# Sheet1.net
KiCad netlist of a schematic drawn in Altium Designer
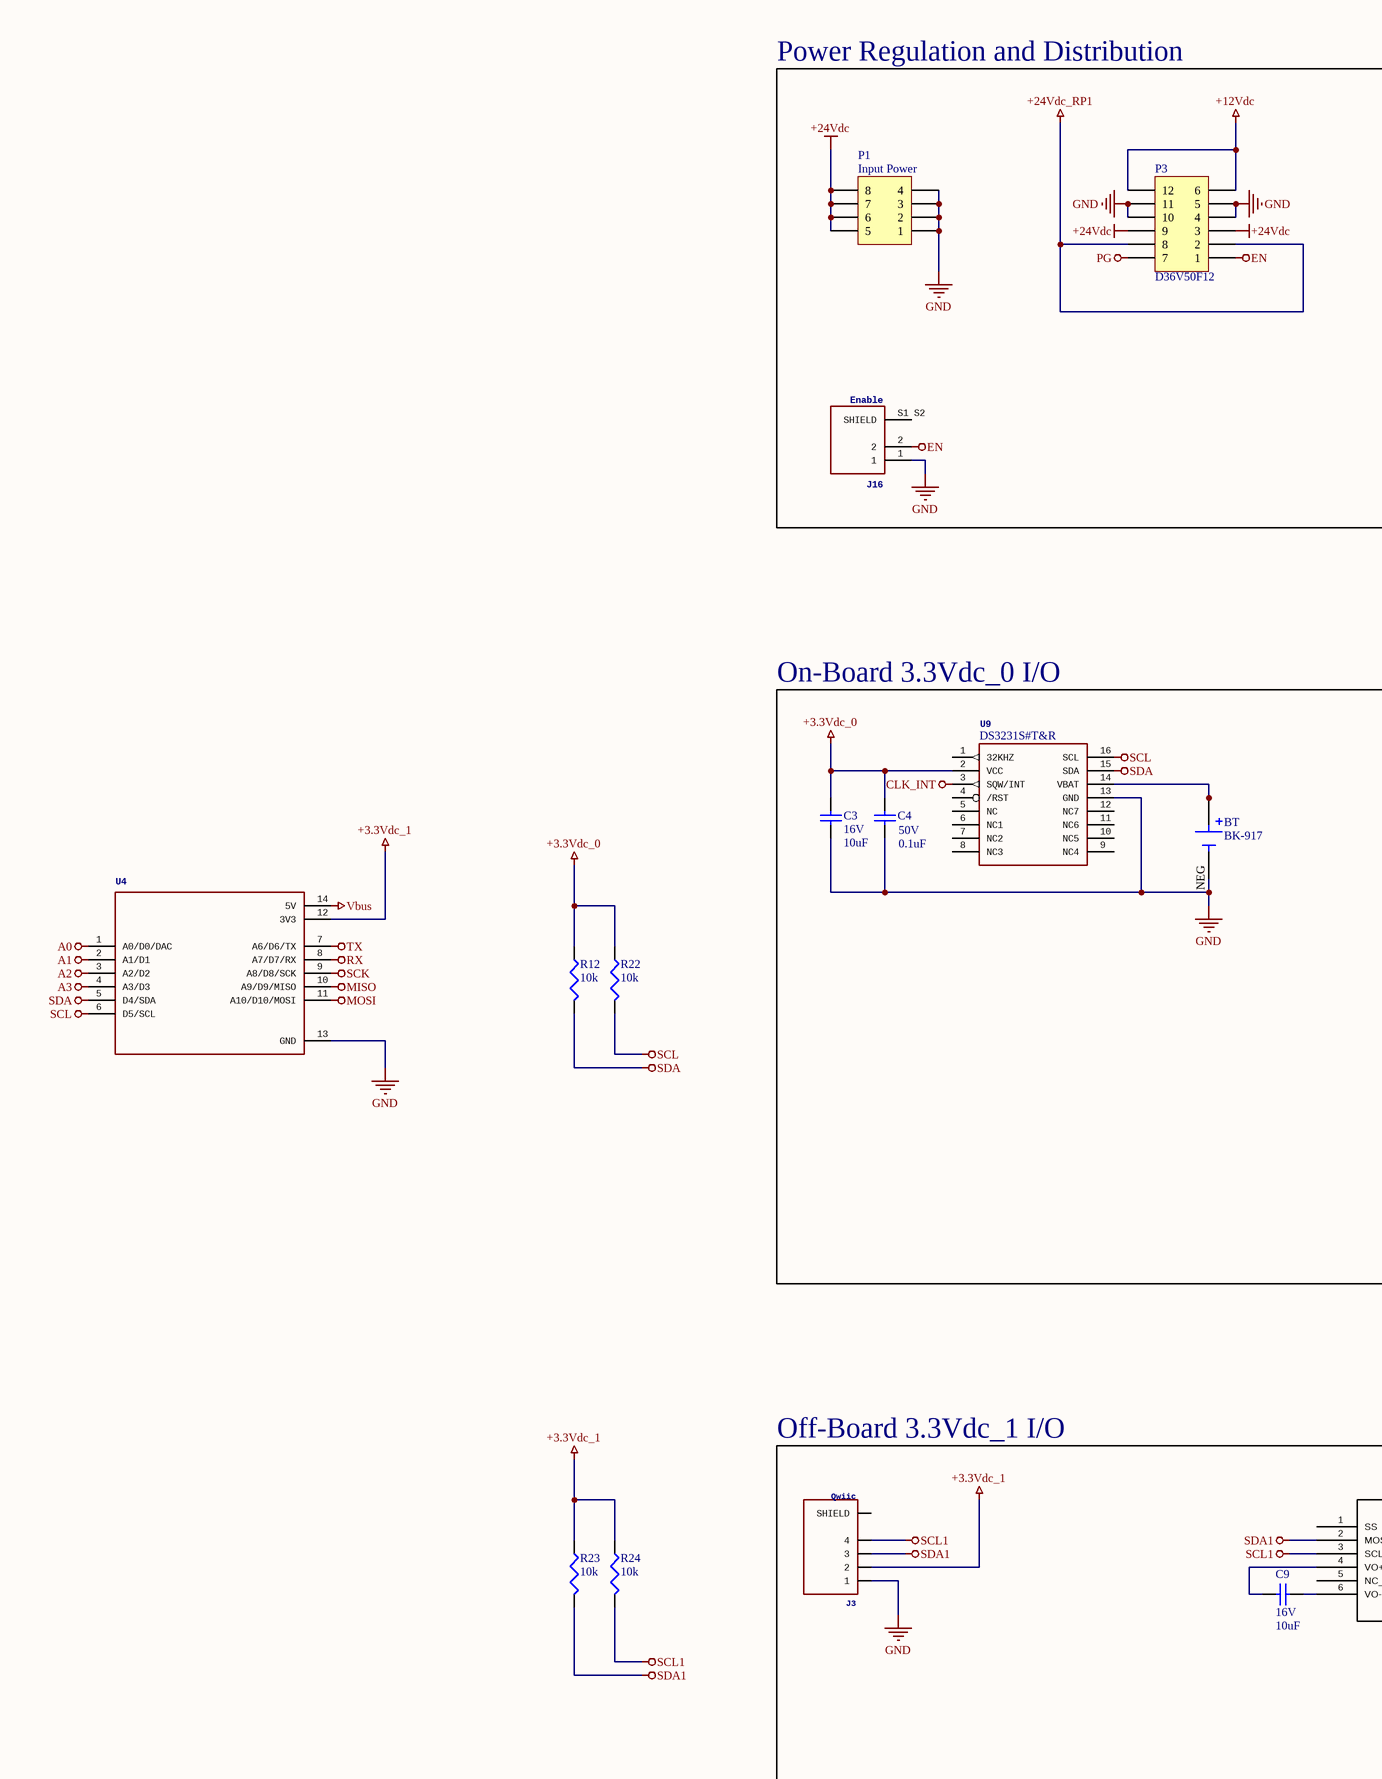
[diagram p0: Sheet1.SchDoc, left]
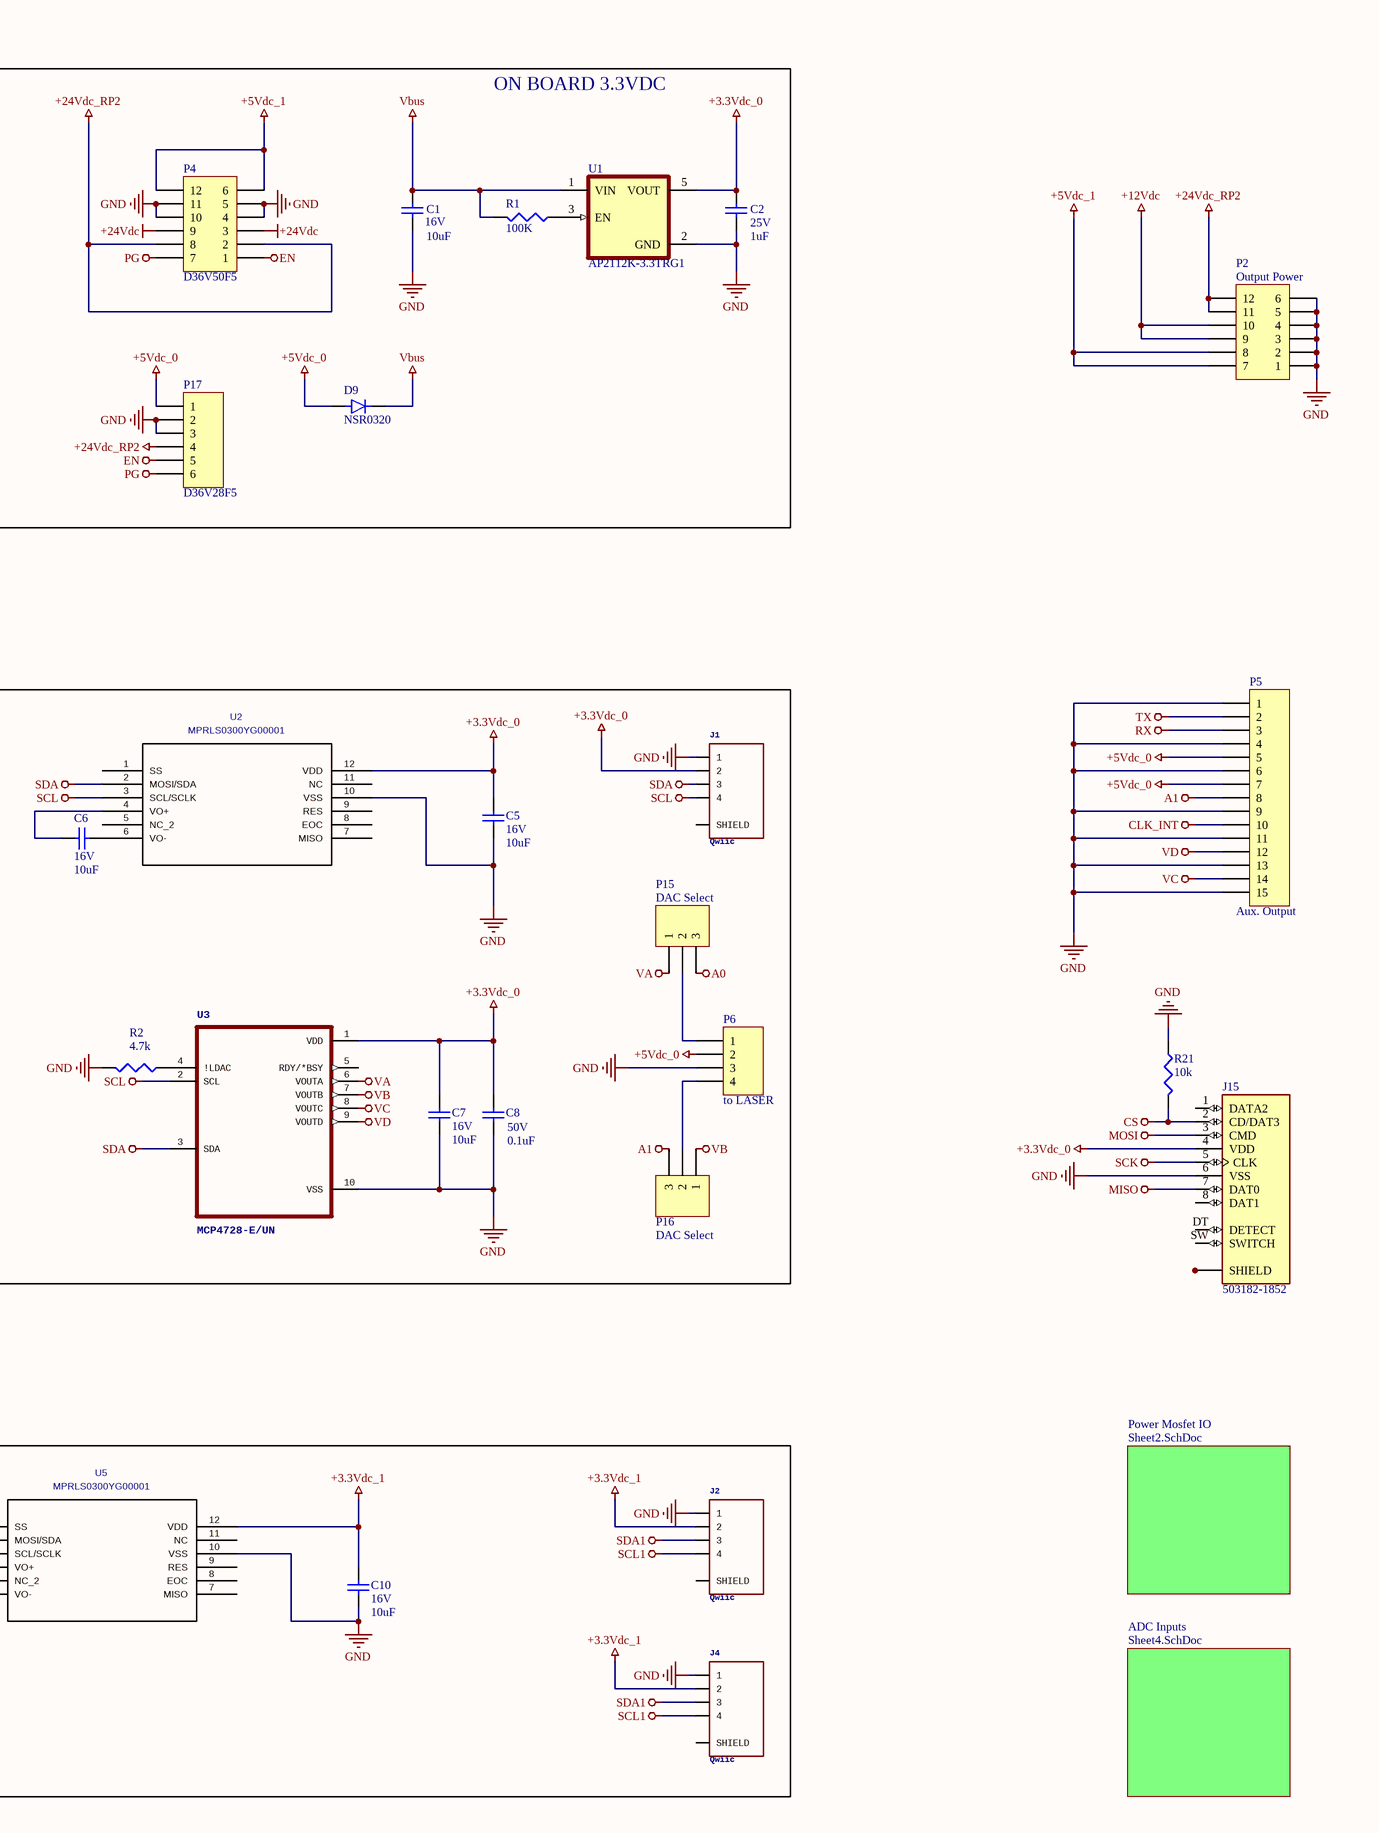
[diagram p1: Sheet1.SchDoc, right]

(export (version "E")
  (design (tool "Eeschema 10.0.6"))
  (components
    (comp (ref "BT")
      (value "BK-917")
      (footprint "BAT_BK-917")
      (description "BATTERY RETAINER COIN PC PIN")
      (fields (field (name "MANUFACTURER") "MPD"))
      (libsource (lib "SnapEDAsch") (part "BK-917"))
    )
    (comp (ref "C1")
      (value "16V")
      (footprint "1608[0603]")
      (description "CAP CER 10UF 16V X5R 0603")
      (fields
        (field (name "ALTIUM_VALUE") "10uF")
        (field (name "MANUFACTURER PART #") "CC0603KRX5R7BB106")
        (field (name "MANUFACTURER") "YAGEO")
      )
      (libsource (lib "Miscellaneous Devices") (part "Cap Semi"))
    )
    (comp (ref "C2")
      (value "25V")
      (footprint "1608[0603]")
      (description "CAP CER 1UF 25V X7R 0603")
      (fields
        (field (name "ALTIUM_VALUE") "1uF")
        (field (name "MANUFACTURER PART #") "AC0603KRX7R8BB105")
        (field (name "MANUFACTURER") "YAGEO")
      )
      (libsource (lib "Miscellaneous Devices") (part "Cap Semi"))
    )
    (comp (ref "C3")
      (value "16V")
      (footprint "1608[0603]")
      (description "CAP CER 10UF 16V X5R 0603")
      (fields
        (field (name "ALTIUM_VALUE") "10uF")
        (field (name "MANUFACTURER PART #") "CC0603KRX5R7BB106")
        (field (name "MANUFACTURER") "YAGEO")
      )
      (libsource (lib "Miscellaneous Devices") (part "Cap Semi"))
    )
    (comp (ref "C4")
      (value "50V")
      (footprint "1608[0603]")
      (description "CAP CER 0.1UF 50V X7R 0603")
      (fields
        (field (name "ALTIUM_VALUE") "0.1uF")
        (field (name "MANUFACTURER PART #") "CC0603KPX7R9BB104")
        (field (name "MANUFACTURER") "YAGEO")
      )
      (libsource (lib "Miscellaneous Devices") (part "Cap Semi"))
    )
    (comp (ref "C5")
      (value "16V")
      (footprint "1608[0603]")
      (description "CAP CER 10UF 16V X5R 0603")
      (fields
        (field (name "ALTIUM_VALUE") "10uF")
        (field (name "MANUFACTURER PART #") "CC0603KRX5R7BB106")
        (field (name "MANUFACTURER") "YAGEO")
      )
      (libsource (lib "Miscellaneous Devices") (part "Cap Semi"))
    )
    (comp (ref "C6")
      (value "16V")
      (footprint "1608[0603]")
      (description "CAP CER 10UF 16V X5R 0603")
      (fields
        (field (name "ALTIUM_VALUE") "10uF")
        (field (name "MANUFACTURER PART #") "CC0603KRX5R7BB106")
        (field (name "MANUFACTURER") "YAGEO")
      )
      (libsource (lib "Miscellaneous Devices") (part "Cap Semi"))
    )
    (comp (ref "C7")
      (value "16V")
      (footprint "1608[0603]")
      (description "CAP CER 10UF 16V X5R 0603")
      (fields
        (field (name "ALTIUM_VALUE") "10uF")
        (field (name "MANUFACTURER PART #") "CC0603KRX5R7BB106")
        (field (name "MANUFACTURER") "YAGEO")
      )
      (libsource (lib "Miscellaneous Devices") (part "Cap Semi"))
    )
    (comp (ref "C8")
      (value "50V")
      (footprint "1608[0603]")
      (description "CAP CER 0.1UF 50V X7R 0603")
      (fields
        (field (name "ALTIUM_VALUE") "0.1uF")
        (field (name "MANUFACTURER PART #") "CC0603KPX7R9BB104")
        (field (name "MANUFACTURER") "YAGEO")
      )
      (libsource (lib "Miscellaneous Devices") (part "Cap Semi"))
    )
    (comp (ref "C9")
      (value "16V")
      (footprint "1608[0603]")
      (description "CAP CER 10UF 16V X5R 0603")
      (fields
        (field (name "ALTIUM_VALUE") "10uF")
        (field (name "MANUFACTURER PART #") "CC0603KRX5R7BB106")
        (field (name "MANUFACTURER") "YAGEO")
      )
      (libsource (lib "Miscellaneous Devices") (part "Cap Semi"))
    )
    (comp (ref "C10")
      (value "16V")
      (footprint "1608[0603]")
      (description "CAP CER 10UF 16V X5R 0603")
      (fields
        (field (name "ALTIUM_VALUE") "10uF")
        (field (name "MANUFACTURER PART #") "CC0603KRX5R7BB106")
        (field (name "MANUFACTURER") "YAGEO")
      )
      (libsource (lib "Miscellaneous Devices") (part "Cap Semi"))
    )
    (comp (ref "D9")
      (value "NSR0320")
      (footprint "DIO_MM3Z3V0T1G")
      (description "DIODE SCHOTTKY 20V 1A SOD323")
      (fields (field (name "MANUFACTURER PART #") "NSR0320MW2T1G") (field (name "MANUFACTURER") "onsemi"))
      (libsource (lib "S1M") (part "S1M"))
    )
    (comp (ref "J1")
      (value "Qwiic")
      (footprint "4P vert")
      (fields
        (field (name "MANUFACTURER PART #") "BM04B-SRSS-TB(LF)(SN)")
        (field (name "MANUFACTURER") "JST Sales")
      )
      (libsource (lib "SM04B-SRSS-TB_LF__SN") (part "SM04B-SRSS-TB(LF)(SN)"))
    )
    (comp (ref "J2")
      (value "Qwiic")
      (footprint "4P vert")
      (fields
        (field (name "MANUFACTURER PART #") "BM04B-SRSS-TB(LF)(SN)")
        (field (name "MANUFACTURER") "JST Sales")
      )
      (libsource (lib "SM04B-SRSS-TB_LF__SN") (part "SM04B-SRSS-TB(LF)(SN)"))
    )
    (comp (ref "J3")
      (value "Qwiic")
      (footprint "JST_SM04B-SRSS-TB(LF)(SN)")
      (fields
        (field (name "MANUFACTURER PART #") "SM04B-SRSS-TB(LF)(SN)")
        (field (name "MANUFACTURER") "JST Sales")
      )
      (libsource (lib "SM04B-SRSS-TB_LF__SN") (part "SM04B-SRSS-TB(LF)(SN)"))
    )
    (comp (ref "J4")
      (value "Qwiic")
      (footprint "JST_SM04B-SRSS-TB(LF)(SN)")
      (fields
        (field (name "MANUFACTURER PART #") "SM04B-SRSS-TB(LF)(SN)")
        (field (name "MANUFACTURER") "JST Sales")
      )
      (libsource (lib "SM04B-SRSS-TB_LF__SN") (part "SM04B-SRSS-TB(LF)(SN)"))
    )
    (comp (ref "J15")
      (value "503182-1852")
      (footprint "MOLEX_503182-1852")
      (description "10 (8 + 2) Position Card Connector Secure Digital - microSDâ„¢ Surface Mount, Right Angle Gold")
      (fields (field (name "MANUFACTURER") "Molex") (field (name "MANUFACTURER PART #") "5031821852"))
      (libsource (lib "503182-1852") (part "503182-1852"))
    )
    (comp (ref "J16")
      (value "Enable")
      (footprint "CONN_BM04B-SRSS-TB(LF)(SN)")
      (fields
        (field (name "MANUFACTURER") "JST Sales")
        (field (name "MANUFACTURER PART #") "BM04B-SRSS-TB(LF)(SN)")
      )
      (libsource (lib "BM02B-SRSS-TB_LF__SN_") (part "BM04B-SRSS-TB(LF)(SN)"))
    )
    (comp (ref "P1")
      (value "Input Power")
      (footprint "2X4 VERTICAL")
      (description "CONN HEADER VERT 8POS 3MM")
      (fields (field (name "MANUFACTURER PART #") "0430450827") (field (name "MANUFACTURER") "Molex"))
      (libsource (lib "Miscellaneous Connectors") (part "Header 4X2A"))
    )
    (comp (ref "P2")
      (value "Output Power")
      (footprint "MOLEX_430451214")
      (description "CONN HEADER VERT 12POS 3MM")
      (fields (field (name "MANUFACTURER PART #") "0430451227") (field (name "MANUFACTURER") "Molex"))
      (libsource (lib "Miscellaneous Connectors") (part "Header 6X2A"))
    )
    (comp (ref "P3")
      (value "D36V50F12")
      (footprint "D36V50FXX, 4.5A")
      (description "DC DC CONVERTER 12V 54W")
      (fields (field (name "VENDOR PART NUMBER") "2183-4095-ND") (field (name "MANUFACTURER") "Pololu"))
      (libsource (lib "Miscellaneous Connectors") (part "Header 6X2A"))
    )
    (comp (ref "P4")
      (value "D36V50F5")
      (footprint "D36V50FXX, 4.5A")
      (description "12V, 4.5A Step-Down Voltage Regulator5V, 5.5A Step-Down Voltage Regulator")
      (fields (field (name "MANUFACTURER") "Pololu"))
      (libsource (lib "Miscellaneous Connectors") (part "Header 6X2A"))
    )
    (comp (ref "P5")
      (value "Aux. Output")
      (footprint "15P VERT")
      (description "Header, 15-Pin")
      (fields
        (field (name "MANUFACTURER PART #") "BM15B-SRSS-TB(LF)(SN)")
        (field (name "MANUFACTURER") "JST Sales America Inc.")
      )
      (libsource (lib "Miscellaneous Connectors") (part "Header 15"))
    )
    (comp (ref "P6")
      (value "to LASER")
      (footprint "4P Mini-SPOX")
      (description "Connector Header Through Hole, Right Angle 4 position 0.098\" (2.50mm)")
      (fields (field (name "MANUFACTURER PART #") "0022057045") (field (name "MANUFACTURER") "Molex"))
      (libsource (lib "Miscellaneous Connectors") (part "Header 4"))
    )
    (comp (ref "P15")
      (value "DAC Select")
      (footprint "HDR1X3")
      (description "Header, 3-Pin")
      (fields
        (field (name "MANUFACTURER PART #") "68000-103HLF")
        (field (name "MANUFACTURER") "Amphenol ICC (FCI)")
      )
      (libsource (lib "") (part "Header 3_1"))
    )
    (comp (ref "P16")
      (value "DAC Select")
      (footprint "HDR1X3")
      (description "Header, 3-Pin")
      (fields
        (field (name "MANUFACTURER PART #") "68000-103HLF")
        (field (name "MANUFACTURER") "Amphenol ICC (FCI)")
      )
      (libsource (lib "Miscellaneous Connectors") (part "Header 3"))
    )
    (comp (ref "P17")
      (value "D36V28F5")
      (footprint "D36V28Fx, 3A")
      (description "5V, 3.2A Step-Down Voltage Regulator")
      (fields (field (name "MANUFACTURER") "Pololu"))
      (libsource (lib "Miscellaneous Connectors") (part "Header 6"))
    )
    (comp (ref "R1")
      (value "100K")
      (footprint "J1-0603")
      (description "RES 100K OHM 1% 1/4W 0603")
      (fields (field (name "MANUFACTURER PART #") "SR0603FR-7T100KL") (field (name "MANUFACTURER") "YAGEO"))
      (libsource (lib "Miscellaneous Devices") (part "Res3"))
    )
    (comp (ref "R2")
      (value "4.7k")
      (footprint "0402")
      (description "RES 4.7K OHM 1% 1/5W 0402")
      (fields (field (name "MANUFACTURER PART #") "SR0402FR-7T4K7L") (field (name "MANUFACTURER") "YAGEO"))
      (libsource (lib "Miscellaneous Devices") (part "Res3"))
    )
    (comp (ref "R12")
      (value "10k")
      (footprint "0402")
      (description "RES 10 KOHM 1% 1/8W 0402")
      (fields (field (name "MANUFACTURER PART #") "AC0402FR-7W10KL") (field (name "MANUFACTURER") "YAGEO"))
      (libsource (lib "Miscellaneous Devices") (part "Res3"))
    )
    (comp (ref "R21")
      (value "10k")
      (footprint "0402")
      (description "RES 10 KOHM 1% 1/8W 0402")
      (fields (field (name "MANUFACTURER PART #") "AC0402FR-7W10KL") (field (name "MANUFACTURER") "YAGEO"))
      (libsource (lib "Miscellaneous Devices") (part "Res3"))
    )
    (comp (ref "R22")
      (value "10k")
      (footprint "0402")
      (description "RES 10 KOHM 1% 1/8W 0402")
      (fields (field (name "MANUFACTURER PART #") "AC0402FR-7W10KL") (field (name "MANUFACTURER") "YAGEO"))
      (libsource (lib "Miscellaneous Devices") (part "Res3"))
    )
    (comp (ref "R23")
      (value "10k")
      (footprint "0402")
      (description "RES 10 KOHM 1% 1/8W 0402")
      (fields (field (name "MANUFACTURER PART #") "AC0402FR-7W10KL") (field (name "MANUFACTURER") "YAGEO"))
      (libsource (lib "Miscellaneous Devices") (part "Res3"))
    )
    (comp (ref "R24")
      (value "10k")
      (footprint "0402")
      (description "RES 10 KOHM 1% 1/8W 0402")
      (fields (field (name "MANUFACTURER PART #") "AC0402FR-7W10KL") (field (name "MANUFACTURER") "YAGEO"))
      (libsource (lib "Miscellaneous Devices") (part "Res3"))
    )
    (comp (ref "U1")
      (value "AP2112K-3.3TRG1")
      (footprint "SOT95P285X140-5N")
      (description "IC REG LINEAR 3.3V 600MA SOT25")
      (fields (field (name "MANUFACTURER") "Diodes Incorporated"))
      (libsource (lib "AP2112K-3.3TRG1") (part "AP2112K-3.3TRG1"))
    )
    (comp (ref "U2")
      (value "MPRLS0300YG00001")
      (footprint "MPRLS0300YG00000")
      (fields
        (field (name "MANUFACTURER") "Honeywell")
        (field (name "MANUFACTURER PART #") "MPRLS0300YG00001B")
      )
      (libsource (lib "MPRLS0300") (part "MPRLS0300YG00001"))
    )
    (comp (ref "U3")
      (value "MCP4728-E/UN")
      (footprint "SOP50P490X110-10N")
      (fields (field (name "MANUFACTURER") "Microchip"))
      (libsource (lib "MCP4728-E_UN") (part "MCP4728-E/UN"))
    )
    (comp (ref "U4")
      (value "Check availability")
      (footprint "MODULE_ADAFRUIT_QT_PY")
      (description "WiFi Dev Board with STEMMA QT - 8 MB Flash / No PSRAM")
      (fields
        (field (name "MANUFACTURER PART #") "QT PY ESP32-S3")
        (field (name "VENDOR PART NUMBER") "5426")
      )
      (libsource (lib "ADAFRUIT_QT_PY") (part "ADAFRUIT_QT_PY"))
    )
    (comp (ref "U5")
      (value "MPRLS0300YG00001")
      (footprint "MPRLS0300YG00000")
      (fields
        (field (name "MANUFACTURER") "Honeywell")
        (field (name "MANUFACTURER PART #") "MPRLS0300YG00001B")
      )
      (libsource (lib "MPRLS0300") (part "MPRLS0300YG00001"))
    )
    (comp (ref "U9")
      (value "DS3231S#T&R")
      (footprint "SO16W")
      (description "Real-Time Clock")
      (fields (field (name "MANUFACTURER") "Maxim"))
      (libsource (lib "DS3231") (part "DS3231/SO"))
    )
  )
  (nets
    (net (code "1") (name "+3.3Vdc_0") (class "Default")
      (node (ref "C2") (pin "2") (pinfunction "2_2") (pintype "passive"))
      (node (ref "C3") (pin "1") (pinfunction "1_1") (pintype "passive"))
      (node (ref "C4") (pin "1") (pinfunction "1_1") (pintype "passive"))
      (node (ref "C5") (pin "1") (pinfunction "1_1") (pintype "passive"))
      (node (ref "C7") (pin "1") (pinfunction "1_1") (pintype "passive"))
      (node (ref "C8") (pin "1") (pinfunction "1_1") (pintype "passive"))
      (node (ref "J1") (pin "2") (pinfunction "2_2") (pintype "passive"))
      (node (ref "J15") (pin "4") (pinfunction "VDD_4") (pintype "power_in"))
      (node (ref "R12") (pin "1") (pinfunction "1_1") (pintype "passive"))
      (node (ref "R22") (pin "1") (pinfunction "1_1") (pintype "passive"))
      (node (ref "U1") (pin "5") (pinfunction "VOUT_5") (pintype "power_in"))
      (node (ref "U2") (pin "12") (pinfunction "VDD_12") (pintype "passive"))
      (node (ref "U3") (pin "1") (pinfunction "VDD_1") (pintype "power_in"))
      (node (ref "U9") (pin "2") (pinfunction "VCC_2") (pintype "power_in"))
    )
    (net (code "2") (name "+3.3Vdc_1") (class "Default")
      (node (ref "C10") (pin "1") (pinfunction "1_1") (pintype "passive"))
      (node (ref "J2") (pin "2") (pinfunction "2_2") (pintype "passive"))
      (node (ref "J3") (pin "2") (pinfunction "2_2") (pintype "passive"))
      (node (ref "J4") (pin "2") (pinfunction "2_2") (pintype "passive"))
      (node (ref "R23") (pin "1") (pinfunction "1_1") (pintype "passive"))
      (node (ref "R24") (pin "1") (pinfunction "1_1") (pintype "passive"))
      (node (ref "U4") (pin "12") (pinfunction "3V3_12") (pintype "power_in"))
      (node (ref "U5") (pin "12") (pinfunction "VDD_12") (pintype "passive"))
    )
    (net (code "3") (name "+5Vdc_0") (class "Default")
      (node (ref "D9") (pin "A") (pinfunction "A_A") (pintype "passive"))
      (node (ref "P17") (pin "1") (pinfunction "1_1") (pintype "passive"))
      (node (ref "P5") (pin "5") (pinfunction "5_5") (pintype "passive"))
      (node (ref "P5") (pin "7") (pinfunction "7_7") (pintype "passive"))
      (node (ref "P6") (pin "2") (pinfunction "2_2") (pintype "passive"))
    )
    (net (code "4") (name "+5Vdc_1") (class "Default")
      (node (ref "P2") (pin "7") (pinfunction "7_7") (pintype "passive"))
      (node (ref "P2") (pin "8") (pinfunction "8_8") (pintype "passive"))
      (node (ref "P4") (pin "12") (pinfunction "12_12") (pintype "passive"))
      (node (ref "P4") (pin "6") (pinfunction "6_6") (pintype "passive"))
    )
    (net (code "5") (name "+12Vdc") (class "Default")
      (node (ref "P2") (pin "10") (pinfunction "10_10") (pintype "passive"))
      (node (ref "P2") (pin "9") (pinfunction "9_9") (pintype "passive"))
      (node (ref "P3") (pin "12") (pinfunction "12_12") (pintype "passive"))
      (node (ref "P3") (pin "6") (pinfunction "6_6") (pintype "passive"))
    )
    (net (code "6") (name "+24Vdc") (class "Default")
      (node (ref "P1") (pin "5") (pinfunction "5_5") (pintype "passive"))
      (node (ref "P1") (pin "6") (pinfunction "6_6") (pintype "passive"))
      (node (ref "P1") (pin "7") (pinfunction "7_7") (pintype "passive"))
      (node (ref "P1") (pin "8") (pinfunction "8_8") (pintype "passive"))
      (node (ref "P3") (pin "3") (pinfunction "3_3") (pintype "passive"))
      (node (ref "P3") (pin "9") (pinfunction "9_9") (pintype "passive"))
      (node (ref "P4") (pin "3") (pinfunction "3_3") (pintype "passive"))
      (node (ref "P4") (pin "9") (pinfunction "9_9") (pintype "passive"))
    )
    (net (code "7") (name "+24Vdc_RP1") (class "Default")
      (node (ref "P3") (pin "2") (pinfunction "2_2") (pintype "passive"))
      (node (ref "P3") (pin "8") (pinfunction "8_8") (pintype "passive"))
    )
    (net (code "8") (name "+24Vdc_RP2") (class "Default")
      (node (ref "P17") (pin "4") (pinfunction "4_4") (pintype "passive"))
      (node (ref "P2") (pin "11") (pinfunction "11_11") (pintype "passive"))
      (node (ref "P2") (pin "12") (pinfunction "12_12") (pintype "passive"))
      (node (ref "P4") (pin "2") (pinfunction "2_2") (pintype "passive"))
      (node (ref "P4") (pin "8") (pinfunction "8_8") (pintype "passive"))
    )
    (net (code "9") (name "A0") (class "Default")
      (node (ref "P15") (pin "3") (pinfunction "3_3") (pintype "passive"))
      (node (ref "U4") (pin "1") (pinfunction "A0/D0/DAC_1") (pintype "passive"))
    )
    (net (code "10") (name "A1") (class "Default")
      (node (ref "P16") (pin "3") (pinfunction "3_3") (pintype "passive"))
      (node (ref "P5") (pin "8") (pinfunction "8_8") (pintype "passive"))
      (node (ref "U4") (pin "2") (pinfunction "A1/D1_2") (pintype "passive"))
    )
    (net (code "11") (name "A2") (class "Default")
      (node (ref "U4") (pin "3") (pinfunction "A2/D2_3") (pintype "passive"))
    )
    (net (code "12") (name "A3") (class "Default")
      (node (ref "U4") (pin "4") (pinfunction "A3/D3_4") (pintype "passive"))
    )
    (net (code "13") (name "CLK_INT") (class "Default")
      (node (ref "P5") (pin "10") (pinfunction "10_10") (pintype "passive"))
      (node (ref "U9") (pin "3") (pinfunction "SQW/INT_3") (pintype "output"))
    )
    (net (code "14") (name "CS") (class "Default")
      (node (ref "J15") (pin "2") (pinfunction "CD/DAT3_2") (pintype "bidirectional"))
      (node (ref "R21") (pin "2") (pinfunction "2_2") (pintype "passive"))
    )
    (net (code "15") (name "EN") (class "Default")
      (node (ref "J16") (pin "2") (pinfunction "2_2") (pintype "passive"))
      (node (ref "P17") (pin "5") (pinfunction "5_5") (pintype "passive"))
      (node (ref "P3") (pin "1") (pinfunction "1_1") (pintype "passive"))
      (node (ref "P4") (pin "1") (pinfunction "1_1") (pintype "passive"))
    )
    (net (code "16") (name "GND") (class "Default")
      (node (ref "BT") (pin "NEG") (pinfunction "NEG_NEG") (pintype "passive"))
      (node (ref "C1") (pin "1") (pinfunction "1_1") (pintype "passive"))
      (node (ref "C10") (pin "2") (pinfunction "2_2") (pintype "passive"))
      (node (ref "C2") (pin "1") (pinfunction "1_1") (pintype "passive"))
      (node (ref "C3") (pin "2") (pinfunction "2_2") (pintype "passive"))
      (node (ref "C4") (pin "2") (pinfunction "2_2") (pintype "passive"))
      (node (ref "C5") (pin "2") (pinfunction "2_2") (pintype "passive"))
      (node (ref "C7") (pin "2") (pinfunction "2_2") (pintype "passive"))
      (node (ref "C8") (pin "2") (pinfunction "2_2") (pintype "passive"))
      (node (ref "J1") (pin "1") (pinfunction "1_1") (pintype "passive"))
      (node (ref "J15") (pin "6") (pinfunction "VSS_6") (pintype "power_in"))
      (node (ref "J16") (pin "1") (pinfunction "1_1") (pintype "passive"))
      (node (ref "J2") (pin "1") (pinfunction "1_1") (pintype "passive"))
      (node (ref "J3") (pin "1") (pinfunction "1_1") (pintype "passive"))
      (node (ref "J4") (pin "1") (pinfunction "1_1") (pintype "passive"))
      (node (ref "P1") (pin "1") (pinfunction "1_1") (pintype "passive"))
      (node (ref "P1") (pin "2") (pinfunction "2_2") (pintype "passive"))
      (node (ref "P1") (pin "3") (pinfunction "3_3") (pintype "passive"))
      (node (ref "P1") (pin "4") (pinfunction "4_4") (pintype "passive"))
      (node (ref "P17") (pin "2") (pinfunction "2_2") (pintype "passive"))
      (node (ref "P17") (pin "3") (pinfunction "3_3") (pintype "passive"))
      (node (ref "P2") (pin "1") (pinfunction "1_1") (pintype "passive"))
      (node (ref "P2") (pin "2") (pinfunction "2_2") (pintype "passive"))
      (node (ref "P2") (pin "3") (pinfunction "3_3") (pintype "passive"))
      (node (ref "P2") (pin "4") (pinfunction "4_4") (pintype "passive"))
      (node (ref "P2") (pin "5") (pinfunction "5_5") (pintype "passive"))
      (node (ref "P2") (pin "6") (pinfunction "6_6") (pintype "passive"))
      (node (ref "P3") (pin "10") (pinfunction "10_10") (pintype "passive"))
      (node (ref "P3") (pin "11") (pinfunction "11_11") (pintype "passive"))
      (node (ref "P3") (pin "4") (pinfunction "4_4") (pintype "passive"))
      (node (ref "P3") (pin "5") (pinfunction "5_5") (pintype "passive"))
      (node (ref "P4") (pin "10") (pinfunction "10_10") (pintype "passive"))
      (node (ref "P4") (pin "11") (pinfunction "11_11") (pintype "passive"))
      (node (ref "P4") (pin "4") (pinfunction "4_4") (pintype "passive"))
      (node (ref "P4") (pin "5") (pinfunction "5_5") (pintype "passive"))
      (node (ref "P5") (pin "1") (pinfunction "1_1") (pintype "passive"))
      (node (ref "P5") (pin "11") (pinfunction "11_11") (pintype "passive"))
      (node (ref "P5") (pin "13") (pinfunction "13_13") (pintype "passive"))
      (node (ref "P5") (pin "15") (pinfunction "15_15") (pintype "passive"))
      (node (ref "P5") (pin "4") (pinfunction "4_4") (pintype "passive"))
      (node (ref "P5") (pin "6") (pinfunction "6_6") (pintype "passive"))
      (node (ref "P5") (pin "9") (pinfunction "9_9") (pintype "passive"))
      (node (ref "P6") (pin "3") (pinfunction "3_3") (pintype "passive"))
      (node (ref "R2") (pin "2") (pinfunction "2_2") (pintype "passive"))
      (node (ref "R21") (pin "1") (pinfunction "1_1") (pintype "passive"))
      (node (ref "U1") (pin "2") (pinfunction "GND_2") (pintype "power_in"))
      (node (ref "U2") (pin "10") (pinfunction "VSS_10") (pintype "passive"))
      (node (ref "U3") (pin "10") (pinfunction "VSS_10") (pintype "power_in"))
      (node (ref "U4") (pin "13") (pinfunction "GND_13") (pintype "power_in"))
      (node (ref "U5") (pin "10") (pinfunction "VSS_10") (pintype "passive"))
      (node (ref "U9") (pin "13") (pinfunction "GND_13") (pintype "power_in"))
    )
    (net (code "17") (name "MISO") (class "Default")
      (node (ref "J15") (pin "7") (pinfunction "DAT0_7") (pintype "bidirectional"))
      (node (ref "U4") (pin "10") (pinfunction "A9/D9/MISO_10") (pintype "passive"))
    )
    (net (code "18") (name "MOSI") (class "Default")
      (node (ref "J15") (pin "3") (pinfunction "CMD_3") (pintype "bidirectional"))
      (node (ref "U4") (pin "11") (pinfunction "A10/D10/MOSI_11") (pintype "passive"))
    )
    (net (code "19") (name "Net-(J15-SHIELD-PadP1)") (class "Default")
      (node (ref "J15") (pin "P1") (pinfunction "SHIELD_P1") (pintype "passive"))
      (node (ref "J15") (pin "P2") (pinfunction "SHIELD_P2") (pintype "passive"))
      (node (ref "J15") (pin "P3") (pinfunction "SHIELD_P3") (pintype "passive"))
      (node (ref "J15") (pin "P4") (pinfunction "SHIELD_P4") (pintype "passive"))
      (node (ref "J15") (pin "P5") (pinfunction "SHIELD_P5") (pintype "passive"))
    )
    (net (code "20") (name "Net-(P15-Pad2)") (class "Default")
      (node (ref "P15") (pin "2") (pinfunction "2_2") (pintype "passive"))
      (node (ref "P6") (pin "1") (pinfunction "1_1") (pintype "passive"))
    )
    (net (code "21") (name "Net-(P16-Pad2)") (class "Default")
      (node (ref "P16") (pin "2") (pinfunction "2_2") (pintype "passive"))
      (node (ref "P6") (pin "4") (pinfunction "4_4") (pintype "passive"))
    )
    (net (code "22") (name "Net-(U1-EN)") (class "Default")
      (node (ref "R1") (pin "1") (pinfunction "1_1") (pintype "passive"))
      (node (ref "U1") (pin "3") (pinfunction "EN_3") (pintype "input"))
    )
    (net (code "23") (name "Net-(U2-VO+)") (class "Default")
      (node (ref "C6") (pin "2") (pinfunction "2_2") (pintype "passive"))
      (node (ref "U2") (pin "4") (pinfunction "VO+_4") (pintype "passive"))
    )
    (net (code "24") (name "Net-(U2-VO-)") (class "Default")
      (node (ref "C6") (pin "1") (pinfunction "1_1") (pintype "passive"))
      (node (ref "U2") (pin "6") (pinfunction "VO-_6") (pintype "passive"))
    )
    (net (code "25") (name "Net-(U3-!LDAC)") (class "Default")
      (node (ref "R2") (pin "1") (pinfunction "1_1") (pintype "passive"))
      (node (ref "U3") (pin "4") (pinfunction "!LDAC_4") (pintype "passive"))
    )
    (net (code "26") (name "Net-(U5-VO+)") (class "Default")
      (node (ref "C9") (pin "1") (pinfunction "1_1") (pintype "passive"))
      (node (ref "U5") (pin "4") (pinfunction "VO+_4") (pintype "passive"))
    )
    (net (code "27") (name "Net-(U5-VO-)") (class "Default")
      (node (ref "C9") (pin "2") (pinfunction "2_2") (pintype "passive"))
      (node (ref "U5") (pin "6") (pinfunction "VO-_6") (pintype "passive"))
    )
    (net (code "28") (name "Net-(U9-VBAT)") (class "Default")
      (node (ref "BT") (pin "1+") (pinfunction "POS_1+") (pintype "passive"))
      (node (ref "BT") (pin "2+") (pinfunction "POS_2+") (pintype "passive"))
      (node (ref "BT") (pin "3+") (pinfunction "POS_3+") (pintype "passive"))
      (node (ref "BT") (pin "4+") (pinfunction "POS_4+") (pintype "passive"))
      (node (ref "U9") (pin "14") (pinfunction "VBAT_14") (pintype "power_in"))
    )
    (net (code "29") (name "PG") (class "Default")
      (node (ref "P17") (pin "6") (pinfunction "6_6") (pintype "passive"))
      (node (ref "P3") (pin "7") (pinfunction "7_7") (pintype "passive"))
      (node (ref "P4") (pin "7") (pinfunction "7_7") (pintype "passive"))
    )
    (net (code "30") (name "RX") (class "Default")
      (node (ref "P5") (pin "3") (pinfunction "3_3") (pintype "passive"))
      (node (ref "U4") (pin "8") (pinfunction "A7/D7/RX_8") (pintype "passive"))
    )
    (net (code "31") (name "SCK") (class "Default")
      (node (ref "J15") (pin "5") (pinfunction "CLK_5") (pintype "bidirectional"))
      (node (ref "U4") (pin "9") (pinfunction "A8/D8/SCK_9") (pintype "passive"))
    )
    (net (code "32") (name "SCL") (class "Default")
      (node (ref "J1") (pin "4") (pinfunction "4_4") (pintype "passive"))
      (node (ref "R22") (pin "2") (pinfunction "2_2") (pintype "passive"))
      (node (ref "U2") (pin "3") (pinfunction "SCL/SCLK_3") (pintype "passive"))
      (node (ref "U3") (pin "2") (pinfunction "SCL_2") (pintype "passive"))
      (node (ref "U4") (pin "6") (pinfunction "D5/SCL_6") (pintype "passive"))
      (node (ref "U9") (pin "16") (pinfunction "SCL_16") (pintype "passive"))
    )
    (net (code "33") (name "SCL1") (class "Default")
      (node (ref "J2") (pin "4") (pinfunction "4_4") (pintype "passive"))
      (node (ref "J3") (pin "4") (pinfunction "4_4") (pintype "passive"))
      (node (ref "J4") (pin "4") (pinfunction "4_4") (pintype "passive"))
      (node (ref "R24") (pin "2") (pinfunction "2_2") (pintype "passive"))
      (node (ref "U5") (pin "3") (pinfunction "SCL/SCLK_3") (pintype "passive"))
    )
    (net (code "34") (name "SDA") (class "Default")
      (node (ref "J1") (pin "3") (pinfunction "3_3") (pintype "passive"))
      (node (ref "R12") (pin "2") (pinfunction "2_2") (pintype "passive"))
      (node (ref "U2") (pin "2") (pinfunction "MOSI/SDA_2") (pintype "passive"))
      (node (ref "U3") (pin "3") (pinfunction "SDA_3") (pintype "passive"))
      (node (ref "U4") (pin "5") (pinfunction "D4/SDA_5") (pintype "passive"))
      (node (ref "U9") (pin "15") (pinfunction "SDA_15") (pintype "passive"))
    )
    (net (code "35") (name "SDA1") (class "Default")
      (node (ref "J2") (pin "3") (pinfunction "3_3") (pintype "passive"))
      (node (ref "J3") (pin "3") (pinfunction "3_3") (pintype "passive"))
      (node (ref "J4") (pin "3") (pinfunction "3_3") (pintype "passive"))
      (node (ref "R23") (pin "2") (pinfunction "2_2") (pintype "passive"))
      (node (ref "U5") (pin "2") (pinfunction "MOSI/SDA_2") (pintype "passive"))
    )
    (net (code "36") (name "TX") (class "Default")
      (node (ref "P5") (pin "2") (pinfunction "2_2") (pintype "passive"))
      (node (ref "U4") (pin "7") (pinfunction "A6/D6/TX_7") (pintype "passive"))
    )
    (net (code "37") (name "VA") (class "Default")
      (node (ref "P15") (pin "1") (pinfunction "1_1") (pintype "passive"))
      (node (ref "U3") (pin "6") (pinfunction "VOUTA_6") (pintype "output"))
    )
    (net (code "38") (name "VB") (class "Default")
      (node (ref "P16") (pin "1") (pinfunction "1_1") (pintype "passive"))
      (node (ref "U3") (pin "7") (pinfunction "VOUTB_7") (pintype "output"))
    )
    (net (code "39") (name "VC") (class "Default")
      (node (ref "P5") (pin "14") (pinfunction "14_14") (pintype "passive"))
      (node (ref "U3") (pin "8") (pinfunction "VOUTC_8") (pintype "output"))
    )
    (net (code "40") (name "VD") (class "Default")
      (node (ref "P5") (pin "12") (pinfunction "12_12") (pintype "passive"))
      (node (ref "U3") (pin "9") (pinfunction "VOUTD_9") (pintype "output"))
    )
    (net (code "41") (name "Vbus") (class "Default")
      (node (ref "C1") (pin "2") (pinfunction "2_2") (pintype "passive"))
      (node (ref "D9") (pin "C") (pinfunction "K_C") (pintype "passive"))
      (node (ref "R1") (pin "2") (pinfunction "2_2") (pintype "passive"))
      (node (ref "U1") (pin "1") (pinfunction "VIN_1") (pintype "power_in"))
      (node (ref "U4") (pin "14") (pinfunction "5V_14") (pintype "power_in"))
    )
    (net (code "42") (name "unconnected-(J1-SHIELD-PadS1_S2)") (class "Default")
      (node (ref "J1") (pin "S1_S2") (pinfunction "SHIELD_S1_S2") (pintype "passive"))
    )
    (net (code "43") (name "unconnected-(J2-SHIELD-PadS1_S2)") (class "Default")
      (node (ref "J2") (pin "S1_S2") (pinfunction "SHIELD_S1_S2") (pintype "passive"))
    )
    (net (code "44") (name "unconnected-(J3-SHIELD-PadS1_S2)") (class "Default")
      (node (ref "J3") (pin "S1_S2") (pinfunction "SHIELD_S1_S2") (pintype "passive"))
    )
    (net (code "45") (name "unconnected-(J4-SHIELD-PadS1_S2)") (class "Default")
      (node (ref "J4") (pin "S1_S2") (pinfunction "SHIELD_S1_S2") (pintype "passive"))
    )
    (net (code "46") (name "unconnected-(J15-DAT1-Pad8)") (class "Default")
      (node (ref "J15") (pin "8") (pinfunction "DAT1_8") (pintype "bidirectional"))
    )
    (net (code "47") (name "unconnected-(J15-DATA2-Pad1)") (class "Default")
      (node (ref "J15") (pin "1") (pinfunction "DATA2_1") (pintype "bidirectional"))
    )
    (net (code "48") (name "unconnected-(J15-DETECT-PadDT)") (class "Default")
      (node (ref "J15") (pin "DT") (pinfunction "DETECT_DT") (pintype "bidirectional"))
    )
    (net (code "49") (name "unconnected-(J15-SWITCH-PadSW)") (class "Default")
      (node (ref "J15") (pin "SW") (pinfunction "SWITCH_SW") (pintype "bidirectional"))
    )
    (net (code "50") (name "unconnected-(J16-SHIELD-PadS1_S2)") (class "Default")
      (node (ref "J16") (pin "S1_S2") (pinfunction "SHIELD_S1_S2") (pintype "passive"))
    )
    (net (code "51") (name "unconnected-(U2-EOC-Pad8)") (class "Default")
      (node (ref "U2") (pin "8") (pinfunction "EOC_8") (pintype "passive"))
    )
    (net (code "52") (name "unconnected-(U2-MISO-Pad7)") (class "Default")
      (node (ref "U2") (pin "7") (pinfunction "MISO_7") (pintype "passive"))
    )
    (net (code "53") (name "unconnected-(U2-NC-Pad11)") (class "Default")
      (node (ref "U2") (pin "11") (pinfunction "NC_11") (pintype "passive"))
    )
    (net (code "54") (name "unconnected-(U2-NC_2-Pad5)") (class "Default")
      (node (ref "U2") (pin "5") (pinfunction "NC_2_5") (pintype "passive"))
    )
    (net (code "55") (name "unconnected-(U2-RES-Pad9)") (class "Default")
      (node (ref "U2") (pin "9") (pinfunction "RES_9") (pintype "passive"))
    )
    (net (code "56") (name "unconnected-(U2-SS-Pad1)") (class "Default")
      (node (ref "U2") (pin "1") (pinfunction "SS_1") (pintype "passive"))
    )
    (net (code "57") (name "unconnected-(U3-RDY{slash}*BSY-Pad5)") (class "Default")
      (node (ref "U3") (pin "5") (pinfunction "RDY/*BSY_5") (pintype "output"))
    )
    (net (code "58") (name "unconnected-(U5-EOC-Pad8)") (class "Default")
      (node (ref "U5") (pin "8") (pinfunction "EOC_8") (pintype "passive"))
    )
    (net (code "59") (name "unconnected-(U5-MISO-Pad7)") (class "Default")
      (node (ref "U5") (pin "7") (pinfunction "MISO_7") (pintype "passive"))
    )
    (net (code "60") (name "unconnected-(U5-NC-Pad11)") (class "Default")
      (node (ref "U5") (pin "11") (pinfunction "NC_11") (pintype "passive"))
    )
    (net (code "61") (name "unconnected-(U5-NC_2-Pad5)") (class "Default")
      (node (ref "U5") (pin "5") (pinfunction "NC_2_5") (pintype "passive"))
    )
    (net (code "62") (name "unconnected-(U5-RES-Pad9)") (class "Default")
      (node (ref "U5") (pin "9") (pinfunction "RES_9") (pintype "passive"))
    )
    (net (code "63") (name "unconnected-(U5-SS-Pad1)") (class "Default")
      (node (ref "U5") (pin "1") (pinfunction "SS_1") (pintype "passive"))
    )
    (net (code "64") (name "unconnected-(U9-32KHZ-Pad1)") (class "Default")
      (node (ref "U9") (pin "1") (pinfunction "32KHZ_1") (pintype "output"))
    )
    (net (code "65") (name "unconnected-(U9-NC-Pad5)") (class "Default")
      (node (ref "U9") (pin "5") (pinfunction "NC_5") (pintype "passive"))
    )
    (net (code "66") (name "unconnected-(U9-NC1-Pad6)") (class "Default")
      (node (ref "U9") (pin "6") (pinfunction "NC1_6") (pintype "passive"))
    )
    (net (code "67") (name "unconnected-(U9-NC2-Pad7)") (class "Default")
      (node (ref "U9") (pin "7") (pinfunction "NC2_7") (pintype "passive"))
    )
    (net (code "68") (name "unconnected-(U9-NC3-Pad8)") (class "Default")
      (node (ref "U9") (pin "8") (pinfunction "NC3_8") (pintype "passive"))
    )
    (net (code "69") (name "unconnected-(U9-NC4-Pad9)") (class "Default")
      (node (ref "U9") (pin "9") (pinfunction "NC4_9") (pintype "passive"))
    )
    (net (code "70") (name "unconnected-(U9-NC5-Pad10)") (class "Default")
      (node (ref "U9") (pin "10") (pinfunction "NC5_10") (pintype "passive"))
    )
    (net (code "71") (name "unconnected-(U9-NC6-Pad11)") (class "Default")
      (node (ref "U9") (pin "11") (pinfunction "NC6_11") (pintype "passive"))
    )
    (net (code "72") (name "unconnected-(U9-NC7-Pad12)") (class "Default")
      (node (ref "U9") (pin "12") (pinfunction "NC7_12") (pintype "passive"))
    )
    (net (code "73") (name "unconnected-(U9-{slash}RST-Pad4)") (class "Default")
      (node (ref "U9") (pin "4") (pinfunction "/RST_4") (pintype "passive"))
    )
  )
)
